# Sheet4.net
KiCad netlist of a schematic drawn in Altium Designer
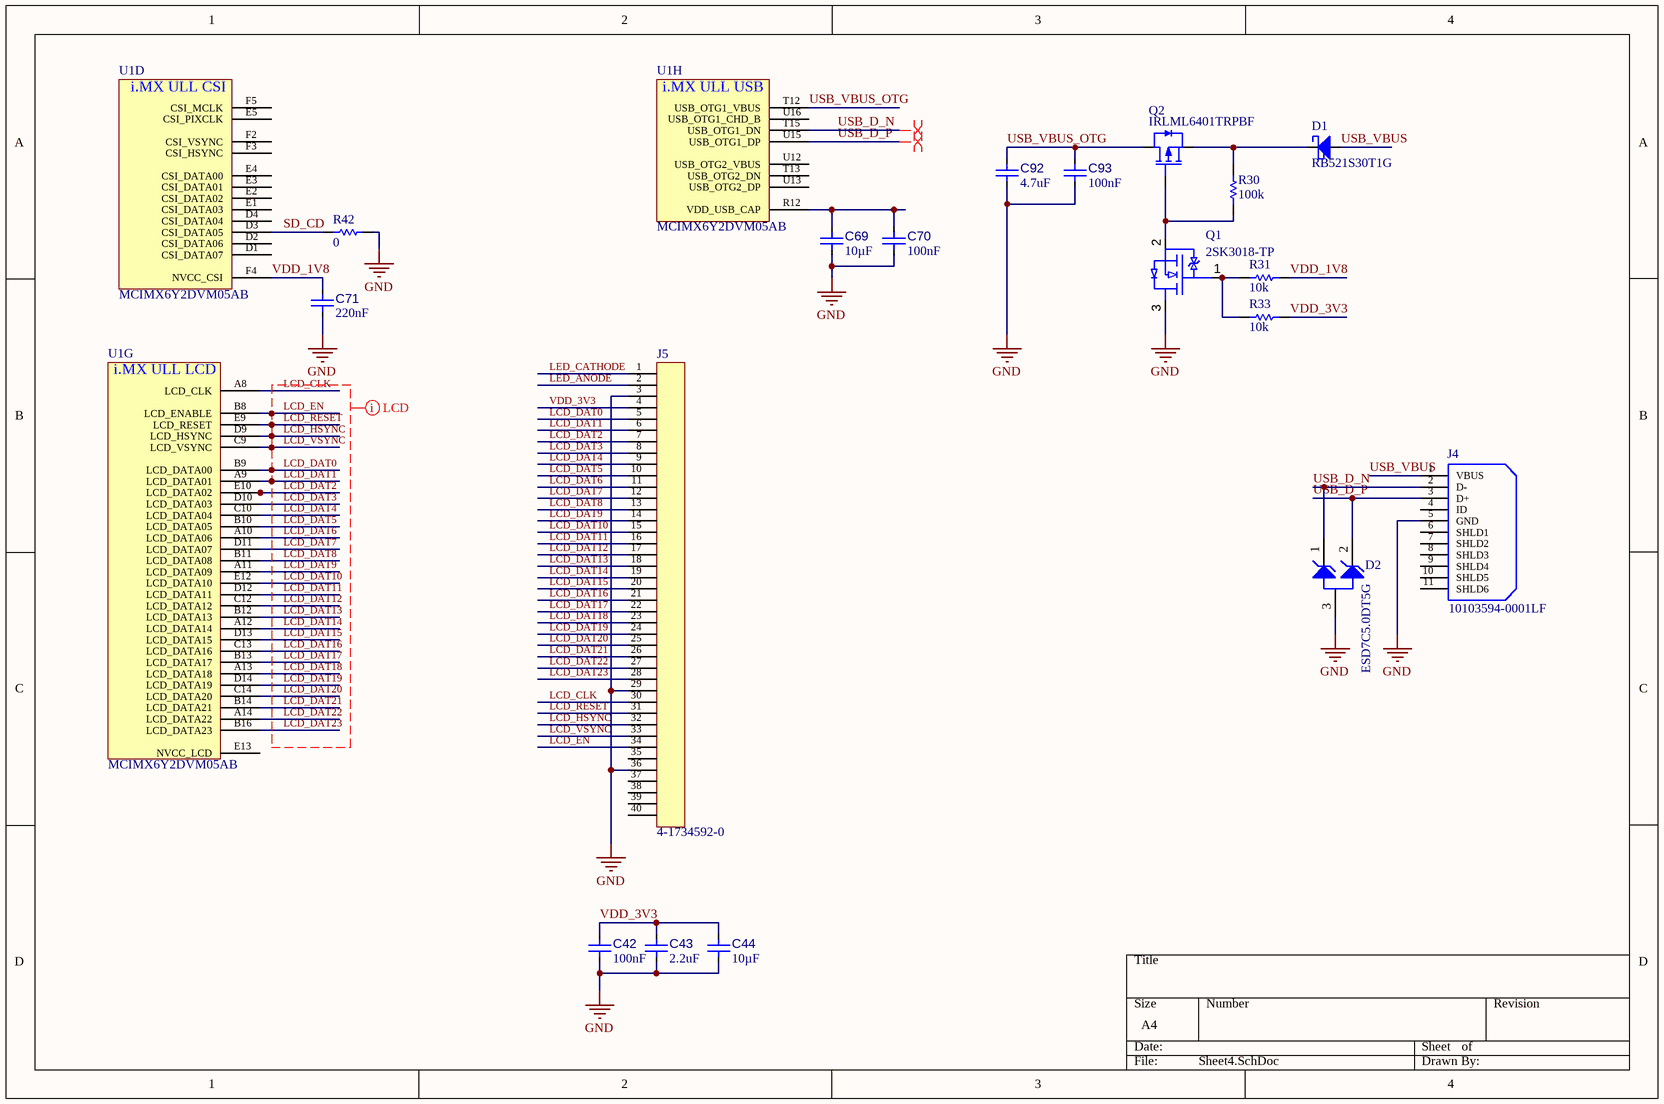
[diagram p0: Sheet4.SchDoc]

(export (version "E")
  (design (tool "Eeschema 10.0.6"))
  (components
    (comp (ref "C42")
      (value "100nF")
      (footprint "0402-SMD-CAP")
      (description "Chip Capacitor, 0.1 uF, +/- 5%, 16 V, 0402 (1005 Metric)")
      (fields (field (name "TOLERANCE") "5%") (field (name "MFR. PART NO.") "EMF105B7104MVHF"))
      (libsource (lib "Budapest University of Technology and Economics") (part "CAP-NP-2"))
    )
    (comp (ref "C43")
      (value "2.2uF")
      (footprint "0603-SMD-CAP")
      (description "CAP CER 2.2UF 10V X7R 0603")
      (fields (field (name "VOLTAGE") "10V") (field (name "TOLERANCE") "10%"))
      (libsource (lib "Budapest University of Technology and Economics") (part "CAP-NP-2"))
    )
    (comp (ref "C44")
      (value "10µF")
      (footprint "0805-SMD-CAP")
      (description "Chip Capacitor, 10 uF, +/- 10%, 16 V, 0805 (2012 Metric)")
      (fields (field (name "TOLERANCE") "10%") (field (name "MFR. PART NO.") "0805YD106KAT2A"))
      (libsource (lib "Budapest University of Technology and Economics") (part "CAP-NP-2"))
    )
    (comp (ref "C69")
      (value "10µF")
      (footprint "0603-SMD-CAP")
      (description "Chip Capacitor, 10µF +/-20%, 10V, 0603, Thickness 1 mm")
      (fields (field (name "TOLERANCE") "10%") (field (name "MFR. PART NO.") "0603ZD106KAT2A"))
      (libsource (lib "Budapest University of Technology and Economics") (part "CAP-NP-2"))
    )
    (comp (ref "C70")
      (value "100nF")
      (footprint "0402-SMD-CAP")
      (description "Chip Capacitor, 0.1 uF, +/- 5%, 16 V, 0402 (1005 Metric)")
      (fields (field (name "TOLERANCE") "5%") (field (name "MFR. PART NO.") "EMF105B7104MVHF"))
      (libsource (lib "Budapest University of Technology and Economics") (part "CAP-NP-2"))
    )
    (comp (ref "C71")
      (value "220nF")
      (footprint "0402-SMD-CAP")
      (fields
        (field (name "TOLERANCE") "10%")
        (field (name "VOLTAGE") "16V")
        (field (name "Comment") "GRM155R71C224KA12D")
      )
      (libsource (lib "Budapest University of Technology and Economics") (part "CAP-NP-2"))
    )
    (comp (ref "C92")
      (value "4.7uF")
      (footprint "0603-SMD-CAP")
      (fields
        (field (name "TOLERANCE") "10%")
        (field (name "VOLTAGE") "6.3V")
        (field (name "Comment") "C0603C475K9PACTU")
      )
      (libsource (lib "Budapest University of Technology and Economics") (part "CAP-NP-2"))
    )
    (comp (ref "C93")
      (value "100nF")
      (footprint "0402-SMD-CAP")
      (description "Chip Capacitor, 0.1 uF, +/- 5%, 16 V, 0402 (1005 Metric)")
      (fields (field (name "TOLERANCE") "5%") (field (name "MFR. PART NO.") "EMF105B7104MVHF"))
      (libsource (lib "Budapest University of Technology and Economics") (part "CAP-NP-2"))
    )
    (comp (ref "D1")
      (value "RB521S30T1G")
      (footprint "ONSC-SOD-523-2-502-01_V")
      (libsource (lib "Budapest University of Technology and Economics") (part "DSKY-AK-2"))
    )
    (comp (ref "D2")
      (value "ESD7C5.0DT5G")
      (footprint "ONSC-SOT-723-3-631AA-01_V")
      (description "ESD Suppressor TVS 15KV 3-Pin SOT-723 T/R")
      (libsource (lib "Budapest University of Technology and Economics") (part "ONSC-K1K2A3-3"))
    )
    (comp (ref "J4")
      (value "10103594-0001LF")
      (footprint "FCI-10103594-0001LF_V")
      (description "Micro USB 2.0 B Receptacle, 5 Position, Height 3.24 mm, -55 to 85 degC, RoHS, Tape and Reel")
      (fields (field (name "MANUFACTURER") "FCI Electronics"))
      (libsource (lib "Budapest University of Technology and Economics") (part "USB-5-6SHLD"))
    )
    (comp (ref "J5")
      (value "4-1734592-0")
      (footprint "4-1734592-0-Footprint-1")
      (libsource (lib "Budapest University of Technology and Economics") (part "4-1734592-0"))
    )
    (comp (ref "Q1")
      (value "2SK3018-TP")
      (footprint "SOT323")
      (description "N-CHANNEL MOSFET, SOT-323 PACKAG")
      (libsource (lib "Budapest University of Technology and Economics") (part "2SK3018-TP"))
    )
    (comp (ref "Q2")
      (value "IRLML6401TRPBF")
      (footprint "SOT323-IRLML6401")
      (description "Trans MOSFET P-CH 12V 4.3A 3-Pin Micro T/R")
      (libsource (lib "Budapest University of Technology and Economics") (part "PEMOS-GSD-3"))
    )
    (comp (ref "R30")
      (value "100k")
      (footprint "0402_SMD_RES")
      (description "Chip Resistor, 100 KOhm, +/- 1%, 0.063 W, -55 to 155 degC, 0402 (1005 Metric)")
      (fields (field (name "POWER") "63mW") (field (name "TOLERANCE") "1%"))
      (libsource (lib "Budapest University of Technology and Economics") (part "RES-2"))
    )
    (comp (ref "R31")
      (value "10k")
      (footprint "0402_SMD_RES")
      (description "Chip Resistor, 10 KOhm, +/- 1%, 63 mW, -55 to 155 degC, 0402 (1005 Metric)")
      (fields (field (name "POWER") "63mW") (field (name "TOLERANCE") "1%"))
      (libsource (lib "Budapest University of Technology and Economics") (part "RES-2"))
    )
    (comp (ref "R33")
      (value "10k")
      (footprint "0402_SMD_RES")
      (description "Chip Resistor, 10 KOhm, +/- 1%, 63 mW, -55 to 155 degC, 0402 (1005 Metric)")
      (fields (field (name "POWER") "63mW") (field (name "TOLERANCE") "1%"))
      (libsource (lib "Budapest University of Technology and Economics") (part "RES-2"))
    )
    (comp (ref "R42")
      (value "0")
      (footprint "0402_SMD_RES")
      (description "Chip Resistor, 0 Ohm, 0.1 W, -55 to 155 degC, 0402 (1005 Metric)")
      (fields (field (name "TOLERANCE") "5%") (field (name "POWER") "100mW"))
      (libsource (lib "Budapest University of Technology and Economics") (part "RES-2"))
    )
    (comp (ref "U1")
      (value "MCIMX6Y2DVM05AB")
      (footprint "BGA100P9X9-81A")
      (libsource (lib "Budapest University of Technology and Economics") (part "MCIMX6Y2DVM05AB"))
    )
  )
  (nets
    (net (code "1") (name "/LCD_CLK") (class "Default")
      (node (ref "J5") (pin "30") (pintype "passive"))
      (node (ref "U1") (pin "A8") (pinfunction "LCD_CLK_A8") (pintype "passive"))
    )
    (net (code "2") (name "/LCD_DAT0") (class "Default")
      (node (ref "J5") (pin "5") (pintype "passive"))
      (node (ref "U1") (pin "B9") (pinfunction "LCD_DATA00_B9") (pintype "passive"))
    )
    (net (code "3") (name "/LCD_DAT1") (class "Default")
      (node (ref "J5") (pin "6") (pintype "passive"))
      (node (ref "U1") (pin "A9") (pinfunction "LCD_DATA01_A9") (pintype "passive"))
    )
    (net (code "4") (name "/LCD_DAT2") (class "Default")
      (node (ref "J5") (pin "7") (pintype "passive"))
      (node (ref "U1") (pin "E10") (pinfunction "LCD_DATA02_E10") (pintype "passive"))
    )
    (net (code "5") (name "/LCD_DAT3") (class "Default")
      (node (ref "J5") (pin "8") (pintype "passive"))
      (node (ref "U1") (pin "D10") (pinfunction "LCD_DATA03_D10") (pintype "passive"))
    )
    (net (code "6") (name "/LCD_DAT4") (class "Default")
      (node (ref "J5") (pin "9") (pintype "passive"))
      (node (ref "U1") (pin "C10") (pinfunction "LCD_DATA04_C10") (pintype "passive"))
    )
    (net (code "7") (name "/LCD_DAT5") (class "Default")
      (node (ref "J5") (pin "10") (pintype "passive"))
      (node (ref "U1") (pin "B10") (pinfunction "LCD_DATA05_B10") (pintype "passive"))
    )
    (net (code "8") (name "/LCD_DAT6") (class "Default")
      (node (ref "J5") (pin "11") (pintype "passive"))
      (node (ref "U1") (pin "A10") (pinfunction "LCD_DATA06_A10") (pintype "passive"))
    )
    (net (code "9") (name "/LCD_DAT7") (class "Default")
      (node (ref "J5") (pin "12") (pintype "passive"))
      (node (ref "U1") (pin "D11") (pinfunction "LCD_DATA07_D11") (pintype "passive"))
    )
    (net (code "10") (name "/LCD_DAT8") (class "Default")
      (node (ref "J5") (pin "13") (pintype "passive"))
      (node (ref "U1") (pin "B11") (pinfunction "LCD_DATA08_B11") (pintype "passive"))
    )
    (net (code "11") (name "/LCD_DAT9") (class "Default")
      (node (ref "J5") (pin "14") (pintype "passive"))
      (node (ref "U1") (pin "A11") (pinfunction "LCD_DATA09_A11") (pintype "passive"))
    )
    (net (code "12") (name "/LCD_DAT10") (class "Default")
      (node (ref "J5") (pin "15") (pintype "passive"))
      (node (ref "U1") (pin "E12") (pinfunction "LCD_DATA10_E12") (pintype "passive"))
    )
    (net (code "13") (name "/LCD_DAT11") (class "Default")
      (node (ref "J5") (pin "16") (pintype "passive"))
      (node (ref "U1") (pin "D12") (pinfunction "LCD_DATA11_D12") (pintype "passive"))
    )
    (net (code "14") (name "/LCD_DAT12") (class "Default")
      (node (ref "J5") (pin "17") (pintype "passive"))
      (node (ref "U1") (pin "C12") (pinfunction "LCD_DATA12_C12") (pintype "passive"))
    )
    (net (code "15") (name "/LCD_DAT13") (class "Default")
      (node (ref "J5") (pin "18") (pintype "passive"))
      (node (ref "U1") (pin "B12") (pinfunction "LCD_DATA13_B12") (pintype "passive"))
    )
    (net (code "16") (name "/LCD_DAT14") (class "Default")
      (node (ref "J5") (pin "19") (pintype "passive"))
      (node (ref "U1") (pin "A12") (pinfunction "LCD_DATA14_A12") (pintype "passive"))
    )
    (net (code "17") (name "/LCD_DAT15") (class "Default")
      (node (ref "J5") (pin "20") (pintype "passive"))
      (node (ref "U1") (pin "D13") (pinfunction "LCD_DATA15_D13") (pintype "passive"))
    )
    (net (code "18") (name "/LCD_DAT16") (class "Default")
      (node (ref "J5") (pin "21") (pintype "passive"))
      (node (ref "U1") (pin "C13") (pinfunction "LCD_DATA16_C13") (pintype "passive"))
    )
    (net (code "19") (name "/LCD_DAT17") (class "Default")
      (node (ref "J5") (pin "22") (pintype "passive"))
      (node (ref "U1") (pin "B13") (pinfunction "LCD_DATA17_B13") (pintype "passive"))
    )
    (net (code "20") (name "/LCD_DAT18") (class "Default")
      (node (ref "J5") (pin "23") (pintype "passive"))
      (node (ref "U1") (pin "A13") (pinfunction "LCD_DATA18_A13") (pintype "passive"))
    )
    (net (code "21") (name "/LCD_DAT19") (class "Default")
      (node (ref "J5") (pin "24") (pintype "passive"))
      (node (ref "U1") (pin "D14") (pinfunction "LCD_DATA19_D14") (pintype "passive"))
    )
    (net (code "22") (name "/LCD_DAT20") (class "Default")
      (node (ref "J5") (pin "25") (pintype "passive"))
      (node (ref "U1") (pin "C14") (pinfunction "LCD_DATA20_C14") (pintype "passive"))
    )
    (net (code "23") (name "/LCD_DAT21") (class "Default")
      (node (ref "J5") (pin "26") (pintype "passive"))
      (node (ref "U1") (pin "B14") (pinfunction "LCD_DATA21_B14") (pintype "passive"))
    )
    (net (code "24") (name "/LCD_DAT22") (class "Default")
      (node (ref "J5") (pin "27") (pintype "passive"))
      (node (ref "U1") (pin "A14") (pinfunction "LCD_DATA22_A14") (pintype "passive"))
    )
    (net (code "25") (name "/LCD_DAT23") (class "Default")
      (node (ref "J5") (pin "28") (pintype "passive"))
      (node (ref "U1") (pin "B16") (pinfunction "LCD_DATA23_B16") (pintype "passive"))
    )
    (net (code "26") (name "/LCD_EN") (class "Default")
      (node (ref "J5") (pin "34") (pintype "passive"))
      (node (ref "U1") (pin "B8") (pinfunction "LCD_ENABLE_B8") (pintype "passive"))
    )
    (net (code "27") (name "/LCD_HSYNC") (class "Default")
      (node (ref "J5") (pin "32") (pintype "passive"))
      (node (ref "U1") (pin "D9") (pinfunction "LCD_HSYNC_D9") (pintype "passive"))
    )
    (net (code "28") (name "/LCD_RESET") (class "Default")
      (node (ref "J5") (pin "31") (pintype "passive"))
      (node (ref "U1") (pin "E9") (pinfunction "LCD_RESET_E9") (pintype "passive"))
    )
    (net (code "29") (name "/LCD_VSYNC") (class "Default")
      (node (ref "J5") (pin "33") (pintype "passive"))
      (node (ref "U1") (pin "C9") (pinfunction "LCD_VSYNC_C9") (pintype "passive"))
    )
    (net (code "30") (name "/LED_ANODE") (class "Default") (node (ref "J5") (pin "2") (pintype "passive")))
    (net (code "31") (name "/LED_CATHODE") (class "Default") (node (ref "J5") (pin "1") (pintype "passive")))
    (net (code "32") (name "/SD_CD") (class "Default")
      (node (ref "R42") (pin "1") (pinfunction "1_1") (pintype "passive"))
      (node (ref "U1") (pin "D3") (pinfunction "CSI_DATA05_D3") (pintype "passive"))
    )
    (net (code "33") (name "/USB_D_N") (class "Default")
      (node (ref "D2") (pin "1") (pinfunction "K1_1") (pintype "passive"))
      (node (ref "J4") (pin "2") (pinfunction "D-_2") (pintype "passive"))
      (node (ref "U1") (pin "T15") (pinfunction "USB_OTG1_DN_T15") (pintype "passive"))
    )
    (net (code "34") (name "/USB_D_P") (class "Default")
      (node (ref "D2") (pin "2") (pinfunction "K2_2") (pintype "passive"))
      (node (ref "J4") (pin "3") (pinfunction "D+_3") (pintype "passive"))
      (node (ref "U1") (pin "U15") (pinfunction "USB_OTG1_DP_U15") (pintype "passive"))
    )
    (net (code "35") (name "/USB_VBUS") (class "Default")
      (node (ref "D1") (pin "1") (pinfunction "A_1") (pintype "passive"))
      (node (ref "J4") (pin "1") (pinfunction "VBUS_1") (pintype "passive"))
    )
    (net (code "36") (name "/USB_VBUS_OTG") (class "Default")
      (node (ref "C92") (pin "1") (pinfunction "1_1") (pintype "passive"))
      (node (ref "C93") (pin "2") (pinfunction "2_2") (pintype "passive"))
      (node (ref "Q2") (pin "3") (pinfunction "DRAIN_3") (pintype "passive"))
      (node (ref "U1") (pin "T12") (pinfunction "USB_OTG1_VBUS_T12") (pintype "passive"))
    )
    (net (code "37") (name "/VDD_1V8") (class "Default")
      (node (ref "C71") (pin "1") (pinfunction "1_1") (pintype "passive"))
      (node (ref "R31") (pin "1") (pinfunction "1_1") (pintype "passive"))
      (node (ref "U1") (pin "F4") (pinfunction "NVCC_CSI_F4") (pintype "passive"))
    )
    (net (code "38") (name "/VDD_3V3") (class "Default")
      (node (ref "C42") (pin "2") (pinfunction "2_2") (pintype "passive"))
      (node (ref "C43") (pin "2") (pinfunction "2_2") (pintype "passive"))
      (node (ref "C44") (pin "1") (pinfunction "1_1") (pintype "passive"))
      (node (ref "J5") (pin "4") (pintype "passive"))
      (node (ref "R33") (pin "1") (pinfunction "1_1") (pintype "passive"))
    )
    (net (code "39") (name "GND") (class "Default")
      (node (ref "C42") (pin "1") (pinfunction "1_1") (pintype "passive"))
      (node (ref "C43") (pin "1") (pinfunction "1_1") (pintype "passive"))
      (node (ref "C44") (pin "2") (pinfunction "2_2") (pintype "passive"))
      (node (ref "C69") (pin "2") (pinfunction "2_2") (pintype "passive"))
      (node (ref "C70") (pin "1") (pinfunction "1_1") (pintype "passive"))
      (node (ref "C71") (pin "2") (pinfunction "2_2") (pintype "passive"))
      (node (ref "C92") (pin "2") (pinfunction "2_2") (pintype "passive"))
      (node (ref "C93") (pin "1") (pinfunction "1_1") (pintype "passive"))
      (node (ref "D2") (pin "3") (pinfunction "A_3") (pintype "passive"))
      (node (ref "J4") (pin "5") (pinfunction "GND_5") (pintype "passive"))
      (node (ref "J5") (pin "29") (pintype "passive"))
      (node (ref "J5") (pin "3") (pintype "passive"))
      (node (ref "J5") (pin "36") (pintype "passive"))
      (node (ref "Q1") (pin "3") (pinfunction "D_3") (pintype "passive"))
      (node (ref "R42") (pin "2") (pinfunction "2_2") (pintype "passive"))
    )
    (net (code "40") (name "Net-(D1-K)") (class "Default")
      (node (ref "D1") (pin "2") (pinfunction "K_2") (pintype "passive"))
      (node (ref "Q2") (pin "2") (pinfunction "SOURCE_2") (pintype "passive"))
      (node (ref "R30") (pin "2") (pinfunction "2_2") (pintype "passive"))
    )
    (net (code "41") (name "Net-(Q1-G)") (class "Default")
      (node (ref "Q1") (pin "1") (pinfunction "G_1") (pintype "passive"))
      (node (ref "R31") (pin "2") (pinfunction "2_2") (pintype "passive"))
      (node (ref "R33") (pin "2") (pinfunction "2_2") (pintype "passive"))
    )
    (net (code "42") (name "Net-(Q1-S)") (class "Default")
      (node (ref "Q1") (pin "2") (pinfunction "S_2") (pintype "passive"))
      (node (ref "Q2") (pin "1") (pinfunction "GATE_1") (pintype "passive"))
      (node (ref "R30") (pin "1") (pinfunction "1_1") (pintype "passive"))
    )
    (net (code "43") (name "Net-(U1H-VDD_USB_CAP)") (class "Default")
      (node (ref "C69") (pin "1") (pinfunction "1_1") (pintype "passive"))
      (node (ref "C70") (pin "2") (pinfunction "2_2") (pintype "passive"))
      (node (ref "U1") (pin "R12") (pinfunction "VDD_USB_CAP_R12") (pintype "passive"))
    )
    (net (code "44") (name "unconnected-(J4-ID-Pad4)") (class "Default")
      (node (ref "J4") (pin "4") (pinfunction "ID_4") (pintype "passive"))
    )
    (net (code "45") (name "unconnected-(J4-SHLD1-Pad6)") (class "Default")
      (node (ref "J4") (pin "6") (pinfunction "SHLD1_6") (pintype "passive"))
    )
    (net (code "46") (name "unconnected-(J4-SHLD2-Pad7)") (class "Default")
      (node (ref "J4") (pin "7") (pinfunction "SHLD2_7") (pintype "passive"))
    )
    (net (code "47") (name "unconnected-(J4-SHLD3-Pad8)") (class "Default")
      (node (ref "J4") (pin "8") (pinfunction "SHLD3_8") (pintype "passive"))
    )
    (net (code "48") (name "unconnected-(J4-SHLD4-Pad9)") (class "Default")
      (node (ref "J4") (pin "9") (pinfunction "SHLD4_9") (pintype "passive"))
    )
    (net (code "49") (name "unconnected-(J4-SHLD5-Pad10)") (class "Default")
      (node (ref "J4") (pin "10") (pinfunction "SHLD5_10") (pintype "passive"))
    )
    (net (code "50") (name "unconnected-(J4-SHLD6-Pad11)") (class "Default")
      (node (ref "J4") (pin "11") (pinfunction "SHLD6_11") (pintype "passive"))
    )
    (net (code "51") (name "unconnected-(J5-Pad35)") (class "Default")
      (node (ref "J5") (pin "35") (pintype "passive"))
    )
    (net (code "52") (name "unconnected-(J5-Pad37)") (class "Default")
      (node (ref "J5") (pin "37") (pintype "passive"))
    )
    (net (code "53") (name "unconnected-(J5-Pad38)") (class "Default")
      (node (ref "J5") (pin "38") (pintype "passive"))
    )
    (net (code "54") (name "unconnected-(J5-Pad39)") (class "Default")
      (node (ref "J5") (pin "39") (pintype "passive"))
    )
    (net (code "55") (name "unconnected-(J5-Pad40)") (class "Default")
      (node (ref "J5") (pin "40") (pintype "passive"))
    )
    (net (code "56") (name "unconnected-(U1D-CSI_DATA00-PadE4)") (class "Default")
      (node (ref "U1") (pin "E4") (pinfunction "CSI_DATA00_E4") (pintype "passive"))
    )
    (net (code "57") (name "unconnected-(U1D-CSI_DATA01-PadE3)") (class "Default")
      (node (ref "U1") (pin "E3") (pinfunction "CSI_DATA01_E3") (pintype "passive"))
    )
    (net (code "58") (name "unconnected-(U1D-CSI_DATA02-PadE2)") (class "Default")
      (node (ref "U1") (pin "E2") (pinfunction "CSI_DATA02_E2") (pintype "passive"))
    )
    (net (code "59") (name "unconnected-(U1D-CSI_DATA03-PadE1)") (class "Default")
      (node (ref "U1") (pin "E1") (pinfunction "CSI_DATA03_E1") (pintype "passive"))
    )
    (net (code "60") (name "unconnected-(U1D-CSI_DATA04-PadD4)") (class "Default")
      (node (ref "U1") (pin "D4") (pinfunction "CSI_DATA04_D4") (pintype "passive"))
    )
    (net (code "61") (name "unconnected-(U1D-CSI_DATA06-PadD2)") (class "Default")
      (node (ref "U1") (pin "D2") (pinfunction "CSI_DATA06_D2") (pintype "passive"))
    )
    (net (code "62") (name "unconnected-(U1D-CSI_DATA07-PadD1)") (class "Default")
      (node (ref "U1") (pin "D1") (pinfunction "CSI_DATA07_D1") (pintype "passive"))
    )
    (net (code "63") (name "unconnected-(U1D-CSI_HSYNC-PadF3)") (class "Default")
      (node (ref "U1") (pin "F3") (pinfunction "CSI_HSYNC_F3") (pintype "passive"))
    )
    (net (code "64") (name "unconnected-(U1D-CSI_MCLK-PadF5)") (class "Default")
      (node (ref "U1") (pin "F5") (pinfunction "CSI_MCLK_F5") (pintype "passive"))
    )
    (net (code "65") (name "unconnected-(U1D-CSI_PIXCLK-PadE5)") (class "Default")
      (node (ref "U1") (pin "E5") (pinfunction "CSI_PIXCLK_E5") (pintype "passive"))
    )
    (net (code "66") (name "unconnected-(U1D-CSI_VSYNC-PadF2)") (class "Default")
      (node (ref "U1") (pin "F2") (pinfunction "CSI_VSYNC_F2") (pintype "passive"))
    )
    (net (code "67") (name "unconnected-(U1G-NVCC_LCD-PadE13)") (class "Default")
      (node (ref "U1") (pin "E13") (pinfunction "NVCC_LCD_E13") (pintype "passive"))
    )
    (net (code "68") (name "unconnected-(U1H-USB_OTG1_CHD_B-PadU16)") (class "Default")
      (node (ref "U1") (pin "U16") (pinfunction "USB_OTG1_CHD_B_U16") (pintype "passive"))
    )
    (net (code "69") (name "unconnected-(U1H-USB_OTG2_DN-PadT13)") (class "Default")
      (node (ref "U1") (pin "T13") (pinfunction "USB_OTG2_DN_T13") (pintype "passive"))
    )
    (net (code "70") (name "unconnected-(U1H-USB_OTG2_DP-PadU13)") (class "Default")
      (node (ref "U1") (pin "U13") (pinfunction "USB_OTG2_DP_U13") (pintype "passive"))
    )
    (net (code "71") (name "unconnected-(U1H-USB_OTG2_VBUS-PadU12)") (class "Default")
      (node (ref "U1") (pin "U12") (pinfunction "USB_OTG2_VBUS_U12") (pintype "passive"))
    )
  )
)
